# MCUStudent.net
KiCad netlist of a schematic drawn in Altium Designer
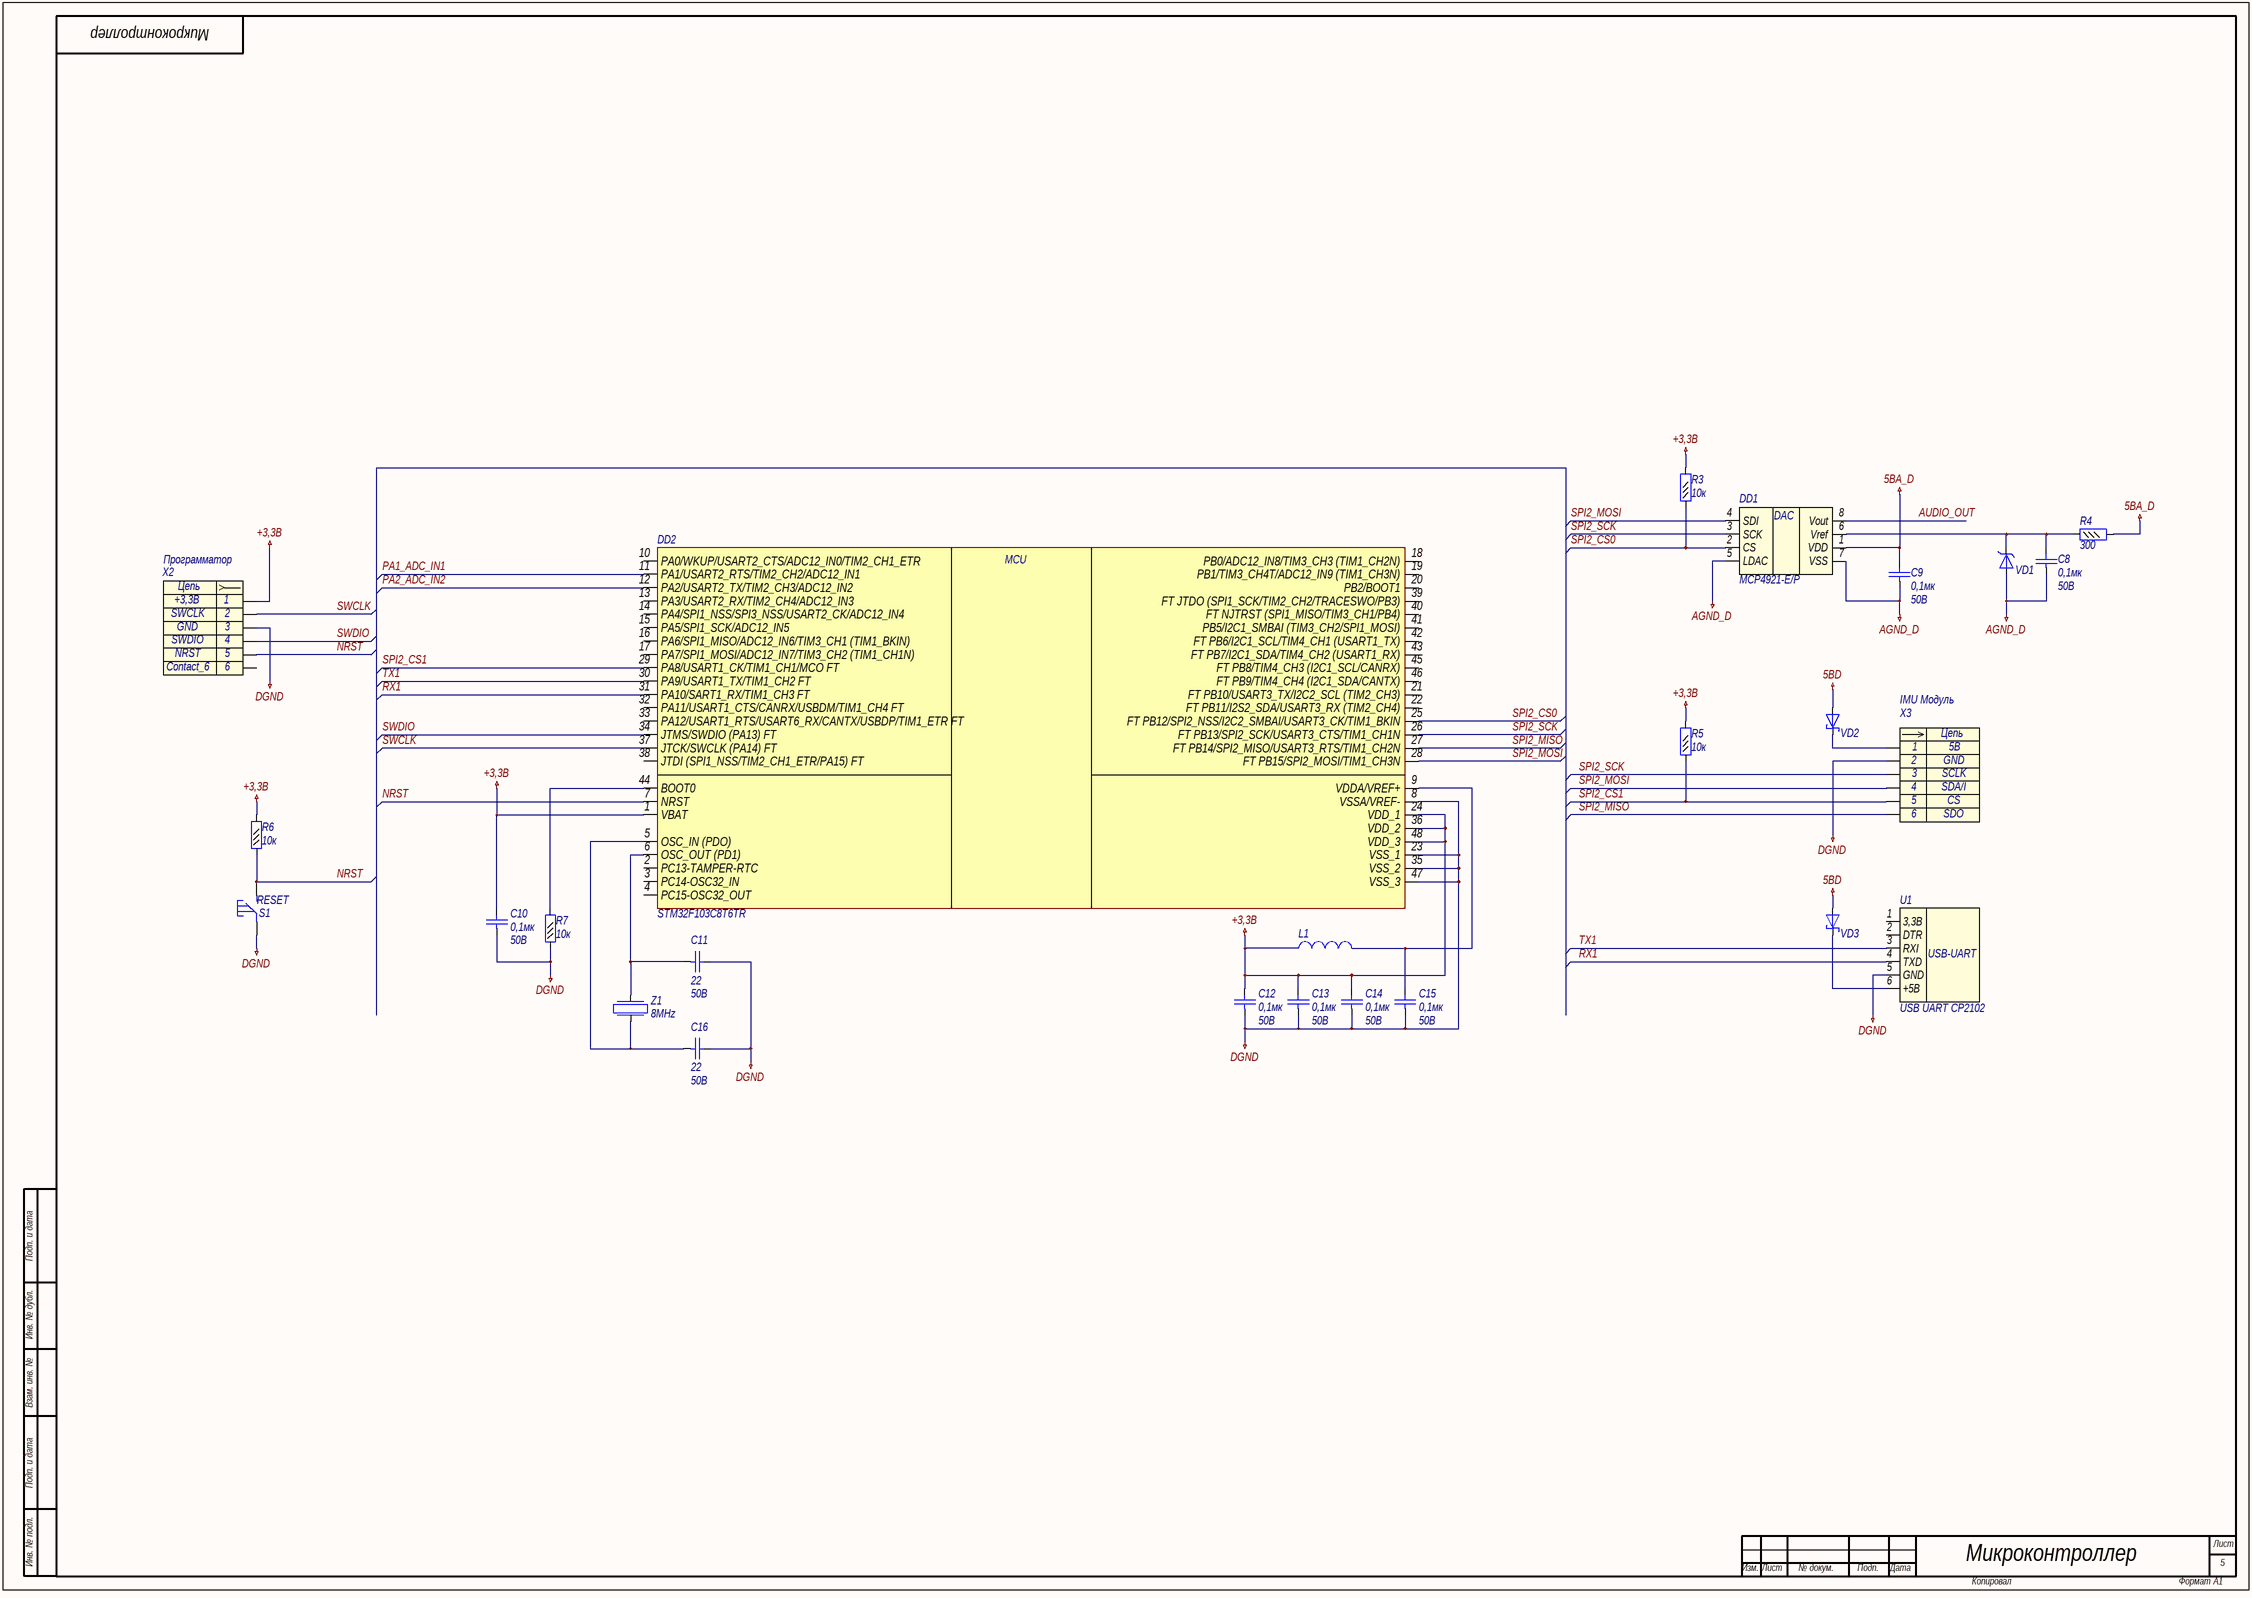
[diagram p0: MCUStudent.SchDoc]

(export (version "E")
  (design (tool "Eeschema 10.0.6"))
  (components
    (comp (ref "C8")
      (value "0,1мк")
      (footprint "C0603")
      (description "Конденсатор")
      (fields
        (field (name "VOLTAGE") "50B")
        (field (name "PART NUMBER") "GRM188R71H104KA93D")
        (field (name "Comment") "Capacitor")
      )
      (libsource (lib "MOP44") (part "Capacitor"))
    )
    (comp (ref "C9")
      (value "0,1мк")
      (footprint "C0603")
      (description "Конденсатор")
      (fields
        (field (name "VOLTAGE") "50B")
        (field (name "PART NUMBER") "GRM188R71H104KA93D")
        (field (name "Comment") "Capacitor")
      )
      (libsource (lib "MOP44") (part "Capacitor"))
    )
    (comp (ref "C10")
      (value "0,1мк")
      (footprint "C0603")
      (description "Конденсатор")
      (fields
        (field (name "VOLTAGE") "50B")
        (field (name "PART NUMBER") "GRM188R71H104KA93D")
        (field (name "Comment") "Capacitor")
      )
      (libsource (lib "MOP44") (part "Capacitor"))
    )
    (comp (ref "C11")
      (value "22")
      (footprint "C0603")
      (description "Конденсатор")
      (fields
        (field (name "VOLTAGE") "50B")
        (field (name "PART NUMBER") "CC0603JRNPO9BN220")
        (field (name "Comment") "Capacitor")
      )
      (libsource (lib "MOP44") (part "Capacitor"))
    )
    (comp (ref "C12")
      (value "0,1мк")
      (footprint "C0603")
      (description "Конденсатор")
      (fields
        (field (name "VOLTAGE") "50B")
        (field (name "PART NUMBER") "GRM188R71H104KA93D")
        (field (name "Comment") "Capacitor")
      )
      (libsource (lib "MOP44") (part "Capacitor"))
    )
    (comp (ref "C13")
      (value "0,1мк")
      (footprint "C0603")
      (description "Конденсатор")
      (fields
        (field (name "VOLTAGE") "50B")
        (field (name "PART NUMBER") "GRM188R71H104KA93D")
        (field (name "Comment") "Capacitor")
      )
      (libsource (lib "MOP44") (part "Capacitor"))
    )
    (comp (ref "C14")
      (value "0,1мк")
      (footprint "C0603")
      (description "Конденсатор")
      (fields
        (field (name "VOLTAGE") "50B")
        (field (name "PART NUMBER") "GRM188R71H104KA93D")
        (field (name "Comment") "Capacitor")
      )
      (libsource (lib "MOP44") (part "Capacitor"))
    )
    (comp (ref "C15")
      (value "0,1мк")
      (footprint "C0603")
      (description "Конденсатор")
      (fields
        (field (name "VOLTAGE") "50B")
        (field (name "PART NUMBER") "GRM188R71H104KA93D")
        (field (name "Comment") "Capacitor")
      )
      (libsource (lib "MOP44") (part "Capacitor"))
    )
    (comp (ref "C16")
      (value "22")
      (footprint "C0603")
      (description "Конденсатор")
      (fields
        (field (name "VOLTAGE") "50B")
        (field (name "PART NUMBER") "CC0603JRNPO9BN220")
        (field (name "Comment") "Capacitor")
      )
      (libsource (lib "MOP44") (part "Capacitor"))
    )
    (comp (ref "DD1")
      (value "MCP4921-E/P")
      (footprint "SO8")
      (description "12-Bit DAC with SPI™ Interface")
      (libsource (lib "MOP44") (part "MCP4921-E/P"))
    )
    (comp (ref "DD2")
      (value "STM32F103C8T6TR")
      (footprint "LQFP48")
      (fields (field (name "PART NUMBER") "STM32F103C8T6TR"))
      (libsource (lib "MOP44") (part "STM32F103C8T6TR"))
    )
    (comp (ref "L1")
      (value "Inductor")
      (footprint "L0603")
      (description "EMI Suppression Filter")
      (fields (field (name "PART NUMBER") "BLM18PG181SN1D"))
      (libsource (lib "MOP44") (part "Inductor"))
    )
    (comp (ref "R3")
      (value "10к")
      (footprint "R0603")
      (description "Резистор")
      (fields (field (name "PART NUMBER") "RC0603FR-0710KL") (field (name "POWER") "0,062Вт"))
      (libsource (lib "MOP44") (part "Resistor_0,062Вт"))
    )
    (comp (ref "R4")
      (value "300")
      (footprint "R0603")
      (description "Резистор")
      (fields (field (name "PART NUMBER") "RC0603FR-07300RL") (field (name "POWER") "0,062Вт"))
      (libsource (lib "") (part "Resistor_0,062Вт_1"))
    )
    (comp (ref "R5")
      (value "10к")
      (footprint "R0603")
      (description "Резистор")
      (fields (field (name "PART NUMBER") "RC0603FR-0710KL") (field (name "POWER") "0,062Вт"))
      (libsource (lib "MOP44") (part "Resistor_0,062Вт"))
    )
    (comp (ref "R6")
      (value "10к")
      (footprint "R0603")
      (description "Резистор")
      (fields (field (name "PART NUMBER") "RC0603FR-0710KL") (field (name "POWER") "0,062Вт"))
      (libsource (lib "MOP44") (part "Resistor_0,062Вт"))
    )
    (comp (ref "R7")
      (value "10к")
      (footprint "R0603")
      (description "Резистор")
      (fields (field (name "PART NUMBER") "RC0603FR-0710KL") (field (name "POWER") "0,062Вт"))
      (libsource (lib "MOP44") (part "Resistor_0,062Вт"))
    )
    (comp (ref "S1")
      (value "RESET")
      (footprint "Button_SMD")
      (description "Кнопка")
      (libsource (lib "MOP44") (part "Button"))
    )
    (comp (ref "U1")
      (value "USB UART")
      (footprint "USB UART CP2102")
      (description "USB UART module cp2102")
      (fields (field (name "PART NAME") "USB UART CP2102"))
      (libsource (lib "MOP44") (part "USB UART"))
    )
    (comp (ref "VD1")
      (value "LM4040BIM3-2.5/NOPB")
      (footprint "SOT23-3")
      (description "Прецезионный источник опорного напряжения")
      (libsource (lib "MOP44") (part "LM4040BIM3-2.5/NOPB"))
    )
    (comp (ref "VD2")
      (value "DiodeSchottky")
      (footprint "SOD-523")
      (description "Диод Шоттки")
      (fields (field (name "PART NUMBER") "PMEG2010AEB.115"))
      (libsource (lib "MOP44") (part "DiodeSchottky"))
    )
    (comp (ref "VD3")
      (value "DiodeSchottky")
      (footprint "SOD-523")
      (description "Диод Шоттки")
      (fields (field (name "PART NUMBER") "PMEG2010AEB.115"))
      (libsource (lib "MOP44") (part "DiodeSchottky"))
    )
    (comp (ref "X2")
      (value "Программатор")
      (footprint "PLS2-6")
      (description "Разъем - 6 конт. розетка")
      (libsource (lib "MOP44") (part "Header_6_sct"))
    )
    (comp (ref "X3")
      (value "IMU Модуль")
      (footprint "PLS-6")
      (description "Разъем - 6 конт. вилка")
      (fields (field (name "PART NUMBER") "MPU-9250"))
      (libsource (lib "MOP44") (part "Header_6_plg"))
    )
    (comp (ref "Z1")
      (value "Crystal")
      (footprint "HC-49S")
      (description "Кварцевый резонатор")
      (fields (field (name "FREQUENCE") "8MHz") (field (name "PART NUMBER") "8.000MHzHC-49US"))
      (libsource (lib "MOP44") (part "Crystal"))
    )
  )
  (nets
    (net (code "1") (name "+3,3В") (class "Default")
      (node (ref "C10") (pin "2") (pinfunction "2_2") (pintype "passive"))
      (node (ref "C12") (pin "2") (pinfunction "2_2") (pintype "passive"))
      (node (ref "C13") (pin "2") (pinfunction "2_2") (pintype "passive"))
      (node (ref "C14") (pin "2") (pinfunction "2_2") (pintype "passive"))
      (node (ref "DD2") (pin "1") (pinfunction "VBAT_1") (pintype "passive"))
      (node (ref "DD2") (pin "24") (pinfunction "VDD_1_24") (pintype "passive"))
      (node (ref "DD2") (pin "36") (pinfunction "VDD_2_36") (pintype "passive"))
      (node (ref "DD2") (pin "48") (pinfunction "VDD_3_48") (pintype "passive"))
      (node (ref "L1") (pin "1") (pinfunction "1_1") (pintype "passive"))
      (node (ref "R3") (pin "2") (pinfunction "2_2") (pintype "passive"))
      (node (ref "R5") (pin "2") (pinfunction "2_2") (pintype "passive"))
      (node (ref "R6") (pin "2") (pinfunction "2_2") (pintype "passive"))
      (node (ref "X2") (pin "1") (pinfunction "1_1") (pintype "passive"))
    )
    (net (code "2") (name "/AUDIO_OUT") (class "Default")
      (node (ref "DD1") (pin "8") (pinfunction "Vout_8") (pintype "power_in"))
    )
    (net (code "3") (name "/NRST") (class "Default")
      (node (ref "DD2") (pin "7") (pinfunction "NRST_7") (pintype "passive"))
      (node (ref "R6") (pin "1") (pinfunction "1_1") (pintype "passive"))
      (node (ref "S1") (pin "4") (pinfunction "4_4") (pintype "passive"))
      (node (ref "X2") (pin "5") (pinfunction "5_5") (pintype "passive"))
    )
    (net (code "4") (name "/PA1_ADC_IN1") (class "Default")
      (node (ref "DD2") (pin "11") (pinfunction "PA1/USART2_RTS/TIM2_CH2/ADC12_IN1_11") (pintype "passive"))
    )
    (net (code "5") (name "/PA2_ADC_IN2") (class "Default")
      (node (ref "DD2") (pin "12") (pinfunction "PA2/USART2_TX/TIM2_CH3/ADC12_IN2_12") (pintype "passive"))
    )
    (net (code "6") (name "/RX1") (class "Default")
      (node (ref "DD2") (pin "31") (pinfunction "PA10/SART1_RX/TIM1_CH3_FT_31") (pintype "passive"))
      (node (ref "U1") (pin "4") (pinfunction "TXD_4") (pintype "power_in"))
    )
    (net (code "7") (name "/SPI2_CS0") (class "Default")
      (node (ref "DD1") (pin "2") (pinfunction "CS_2") (pintype "power_in"))
      (node (ref "DD2") (pin "25") (pinfunction "FT_PB12/SPI2_NSS/I2C2_SMBAI/USART3_CK/TIM1_BKIN_25") (pintype "passive"))
      (node (ref "R3") (pin "1") (pinfunction "1_1") (pintype "passive"))
    )
    (net (code "8") (name "/SPI2_CS1") (class "Default")
      (node (ref "DD2") (pin "29") (pinfunction "PA8/USART1_CK/TIM1_CH1/MCO_FT_29") (pintype "passive"))
      (node (ref "R5") (pin "1") (pinfunction "1_1") (pintype "passive"))
      (node (ref "X3") (pin "5") (pinfunction "5_5") (pintype "passive"))
    )
    (net (code "9") (name "/SPI2_MISO") (class "Default")
      (node (ref "DD2") (pin "27") (pinfunction "FT_PB14/SPI2_MISO/USART3_RTS/TIM1_CH2N_27") (pintype "passive"))
      (node (ref "X3") (pin "6") (pinfunction "6_6") (pintype "passive"))
    )
    (net (code "10") (name "/SPI2_MOSI") (class "Default")
      (node (ref "DD1") (pin "4") (pinfunction "SDI_4") (pintype "power_in"))
      (node (ref "DD2") (pin "28") (pinfunction "FT_PB15/SPI2_MOSI/TIM1_CH3N_28") (pintype "passive"))
      (node (ref "X3") (pin "4") (pinfunction "4_4") (pintype "passive"))
    )
    (net (code "11") (name "/SPI2_SCK") (class "Default")
      (node (ref "DD1") (pin "3") (pinfunction "SCK_3") (pintype "power_in"))
      (node (ref "DD2") (pin "26") (pinfunction "FT_PB13/SPI2_SCK/USART3_CTS/TIM1_CH1N_26") (pintype "passive"))
      (node (ref "X3") (pin "3") (pinfunction "3_3") (pintype "passive"))
    )
    (net (code "12") (name "/SWCLK") (class "Default")
      (node (ref "DD2") (pin "37") (pinfunction "JTCK/SWCLK_(PA14)_FT_37") (pintype "passive"))
      (node (ref "X2") (pin "2") (pinfunction "2_2") (pintype "passive"))
    )
    (net (code "13") (name "/SWDIO") (class "Default")
      (node (ref "DD2") (pin "34") (pinfunction "JTMS/SWDIO_(PA13)_FT_34") (pintype "passive"))
      (node (ref "X2") (pin "4") (pinfunction "4_4") (pintype "passive"))
    )
    (net (code "14") (name "/TX1") (class "Default")
      (node (ref "DD2") (pin "30") (pinfunction "PA9/USART1_TX/TIM1_CH2_FT_30") (pintype "passive"))
      (node (ref "U1") (pin "3") (pinfunction "RXI_3") (pintype "power_in"))
    )
    (net (code "15") (name "5BA_D") (class "Default")
      (node (ref "C9") (pin "2") (pinfunction "2_2") (pintype "passive"))
      (node (ref "DD1") (pin "1") (pinfunction "VDD_1") (pintype "power_in"))
      (node (ref "R4") (pin "2") (pinfunction "2_2") (pintype "passive"))
    )
    (net (code "16") (name "5BD") (class "Default")
      (node (ref "VD2") (pin "2") (pinfunction "A_2") (pintype "passive"))
      (node (ref "VD3") (pin "2") (pinfunction "A_2") (pintype "passive"))
    )
    (net (code "17") (name "AGND_D") (class "Default")
      (node (ref "C8") (pin "1") (pinfunction "1_1") (pintype "passive"))
      (node (ref "C9") (pin "1") (pinfunction "1_1") (pintype "passive"))
      (node (ref "DD1") (pin "5") (pinfunction "LDAC_5") (pintype "power_in"))
      (node (ref "DD1") (pin "7") (pinfunction "VSS_7") (pintype "power_in"))
      (node (ref "VD1") (pin "2") (pinfunction "A_2") (pintype "passive"))
    )
    (net (code "18") (name "DGND") (class "Default")
      (node (ref "C10") (pin "1") (pinfunction "1_1") (pintype "passive"))
      (node (ref "C11") (pin "2") (pinfunction "2_2") (pintype "passive"))
      (node (ref "C12") (pin "1") (pinfunction "1_1") (pintype "passive"))
      (node (ref "C13") (pin "1") (pinfunction "1_1") (pintype "passive"))
      (node (ref "C14") (pin "1") (pinfunction "1_1") (pintype "passive"))
      (node (ref "C15") (pin "1") (pinfunction "1_1") (pintype "passive"))
      (node (ref "C16") (pin "2") (pinfunction "2_2") (pintype "passive"))
      (node (ref "DD2") (pin "23") (pinfunction "VSS_1_23") (pintype "passive"))
      (node (ref "DD2") (pin "35") (pinfunction "VSS_2_35") (pintype "passive"))
      (node (ref "DD2") (pin "47") (pinfunction "VSS_3_47") (pintype "passive"))
      (node (ref "DD2") (pin "8") (pinfunction "VSSA/VREF-_8") (pintype "passive"))
      (node (ref "R7") (pin "1") (pinfunction "1_1") (pintype "passive"))
      (node (ref "S1") (pin "1") (pinfunction "1_1") (pintype "passive"))
      (node (ref "U1") (pin "5") (pinfunction "GND_5") (pintype "power_in"))
      (node (ref "X2") (pin "3") (pinfunction "3_3") (pintype "passive"))
      (node (ref "X3") (pin "2") (pinfunction "2_2") (pintype "passive"))
    )
    (net (code "19") (name "Net-(DD1-Vref)") (class "Default")
      (node (ref "C8") (pin "2") (pinfunction "2_2") (pintype "passive"))
      (node (ref "DD1") (pin "6") (pinfunction "Vref_6") (pintype "power_in"))
      (node (ref "R4") (pin "1") (pinfunction "1_1") (pintype "passive"))
      (node (ref "VD1") (pin "1") (pinfunction "K_1") (pintype "passive"))
    )
    (net (code "20") (name "Net-(DD2-BOOT0)") (class "Default")
      (node (ref "DD2") (pin "44") (pinfunction "BOOT0_44") (pintype "passive"))
      (node (ref "R7") (pin "2") (pinfunction "2_2") (pintype "passive"))
    )
    (net (code "21") (name "Net-(DD2-OSC_IN_(PDO))") (class "Default")
      (node (ref "C16") (pin "1") (pinfunction "1_1") (pintype "passive"))
      (node (ref "DD2") (pin "5") (pinfunction "OSC_IN_(PDO)_5") (pintype "passive"))
      (node (ref "Z1") (pin "1") (pinfunction "1_1") (pintype "passive"))
    )
    (net (code "22") (name "Net-(DD2-OSC_OUT_(PD1))") (class "Default")
      (node (ref "C11") (pin "1") (pinfunction "1_1") (pintype "passive"))
      (node (ref "DD2") (pin "6") (pinfunction "OSC_OUT_(PD1)_6") (pintype "passive"))
      (node (ref "Z1") (pin "2") (pinfunction "2_2") (pintype "passive"))
    )
    (net (code "23") (name "Net-(DD2-VDDA{slash}VREF+)") (class "Default")
      (node (ref "C15") (pin "2") (pinfunction "2_2") (pintype "passive"))
      (node (ref "DD2") (pin "9") (pinfunction "VDDA/VREF+_9") (pintype "passive"))
      (node (ref "L1") (pin "2") (pinfunction "2_2") (pintype "passive"))
    )
    (net (code "24") (name "Net-(U1-+5B)") (class "Default")
      (node (ref "U1") (pin "6") (pinfunction "+5B_6") (pintype "power_in"))
      (node (ref "VD3") (pin "1") (pinfunction "K_1") (pintype "passive"))
    )
    (net (code "25") (name "Net-(VD2-K)") (class "Default")
      (node (ref "VD2") (pin "1") (pinfunction "K_1") (pintype "passive"))
      (node (ref "X3") (pin "1") (pinfunction "1_1") (pintype "passive"))
    )
    (net (code "26") (name "unconnected-(DD2-FT_JTDO_(SPI1_SCK{slash}TIM2_CH2{slash}TRACESWO{slash}PB3)-Pad39)") (class "Default")
      (node (ref "DD2") (pin "39") (pinfunction "FT_JTDO_(SPI1_SCK/TIM2_CH2/TRACESWO/PB3)_39") (pintype "passive"))
    )
    (net (code "27") (name "unconnected-(DD2-FT_NJTRST_(SPI1_MISO{slash}TIM3_CH1{slash}PB4)-Pad40)") (class "Default")
      (node (ref "DD2") (pin "40") (pinfunction "FT_NJTRST_(SPI1_MISO/TIM3_CH1/PB4)_40") (pintype "passive"))
    )
    (net (code "28") (name "unconnected-(DD2-FT_PB6{slash}I2C1_SCL{slash}TIM4_CH1_(USART1_TX)-Pad42)") (class "Default")
      (node (ref "DD2") (pin "42") (pinfunction "FT_PB6/I2C1_SCL/TIM4_CH1_(USART1_TX)_42") (pintype "passive"))
    )
    (net (code "29") (name "unconnected-(DD2-FT_PB7{slash}I2C1_SDA{slash}TIM4_CH2_(USART1_RX)-Pad43)") (class "Default")
      (node (ref "DD2") (pin "43") (pinfunction "FT_PB7/I2C1_SDA/TIM4_CH2_(USART1_RX)_43") (pintype "passive"))
    )
    (net (code "30") (name "unconnected-(DD2-FT_PB8{slash}TIM4_CH3_(I2C1_SCL{slash}CANRX)-Pad45)") (class "Default")
      (node (ref "DD2") (pin "45") (pinfunction "FT_PB8/TIM4_CH3_(I2C1_SCL/CANRX)_45") (pintype "passive"))
    )
    (net (code "31") (name "unconnected-(DD2-FT_PB9{slash}TIM4_CH4_(I2C1_SDA{slash}CANTX)-Pad46)") (class "Default")
      (node (ref "DD2") (pin "46") (pinfunction "FT_PB9/TIM4_CH4_(I2C1_SDA/CANTX)_46") (pintype "passive"))
    )
    (net (code "32") (name "unconnected-(DD2-FT_PB10{slash}USART3_TX{slash}I2C2_SCL_(TIM2_CH3)-Pad21)") (class "Default")
      (node (ref "DD2") (pin "21") (pinfunction "FT_PB10/USART3_TX/I2C2_SCL_(TIM2_CH3)_21") (pintype "passive"))
    )
    (net (code "33") (name "unconnected-(DD2-FT_PB11{slash}I2S2_SDA{slash}USART3_RX_(TIM2_CH4)-Pad22)") (class "Default")
      (node (ref "DD2") (pin "22") (pinfunction "FT_PB11/I2S2_SDA/USART3_RX_(TIM2_CH4)_22") (pintype "passive"))
    )
    (net (code "34") (name "unconnected-(DD2-JTDI_(SPI1_NSS{slash}TIM2_CH1_ETR{slash}PA15)_FT-Pad38)") (class "Default")
      (node (ref "DD2") (pin "38") (pinfunction "JTDI_(SPI1_NSS/TIM2_CH1_ETR/PA15)_FT_38") (pintype "passive"))
    )
    (net (code "35") (name "unconnected-(DD2-PA0{slash}WKUP{slash}USART2_CTS{slash}ADC12_IN0{slash}TIM2_CH1_ETR-Pad10)") (class "Default")
      (node (ref "DD2") (pin "10") (pinfunction "PA0/WKUP/USART2_CTS/ADC12_IN0/TIM2_CH1_ETR_10") (pintype "passive"))
    )
    (net (code "36") (name "unconnected-(DD2-PA3{slash}USART2_RX{slash}TIM2_CH4{slash}ADC12_IN3-Pad13)") (class "Default")
      (node (ref "DD2") (pin "13") (pinfunction "PA3/USART2_RX/TIM2_CH4/ADC12_IN3_13") (pintype "passive"))
    )
    (net (code "37") (name "unconnected-(DD2-PA4{slash}SPI1_NSS{slash}SPI3_NSS{slash}USART2_CK{slash}ADC12_IN4-Pad14)") (class "Default")
      (node (ref "DD2") (pin "14") (pinfunction "PA4/SPI1_NSS/SPI3_NSS/USART2_CK/ADC12_IN4_14") (pintype "passive"))
    )
    (net (code "38") (name "unconnected-(DD2-PA5{slash}SPI1_SCK{slash}ADC12_IN5-Pad15)") (class "Default")
      (node (ref "DD2") (pin "15") (pinfunction "PA5/SPI1_SCK/ADC12_IN5_15") (pintype "passive"))
    )
    (net (code "39") (name "unconnected-(DD2-PA6{slash}SPI1_MISO{slash}ADC12_IN6{slash}TIM3_CH1_(TIM1_BKIN)-Pad16)") (class "Default")
      (node (ref "DD2") (pin "16") (pinfunction "PA6/SPI1_MISO/ADC12_IN6/TIM3_CH1_(TIM1_BKIN)_16") (pintype "passive"))
    )
    (net (code "40") (name "unconnected-(DD2-PA7{slash}SPI1_MOSI{slash}ADC12_IN7{slash}TIM3_CH2_(TIM1_CH1N)-Pad17)") (class "Default")
      (node (ref "DD2") (pin "17") (pinfunction "PA7/SPI1_MOSI/ADC12_IN7/TIM3_CH2_(TIM1_CH1N)_17") (pintype "passive"))
    )
    (net (code "41") (name "unconnected-(DD2-PA11{slash}USART1_CTS{slash}CANRX{slash}USBDM{slash}TIM1_CH4_FT-Pad32)") (class "Default")
      (node (ref "DD2") (pin "32") (pinfunction "PA11/USART1_CTS/CANRX/USBDM/TIM1_CH4_FT_32") (pintype "passive"))
    )
    (net (code "42") (name "unconnected-(DD2-PA12{slash}USART1_RTS{slash}USART6_RX{slash}CANTX{slash}USBDP{slash}TIM1_ETR_FT-Pad33)") (class "Default")
      (node (ref "DD2") (pin "33") (pinfunction "PA12/USART1_RTS/USART6_RX/CANTX/USBDP/TIM1_ETR_FT_33") (pintype "passive"))
    )
    (net (code "43") (name "unconnected-(DD2-PB0{slash}ADC12_IN8{slash}TIM3_CH3_(TIM1_CH2N)-Pad18)") (class "Default")
      (node (ref "DD2") (pin "18") (pinfunction "PB0/ADC12_IN8/TIM3_CH3_(TIM1_CH2N)_18") (pintype "passive"))
    )
    (net (code "44") (name "unconnected-(DD2-PB1{slash}TIM3_CH4T{slash}ADC12_IN9_(TIM1_CH3N)-Pad19)") (class "Default")
      (node (ref "DD2") (pin "19") (pinfunction "PB1/TIM3_CH4T/ADC12_IN9_(TIM1_CH3N)_19") (pintype "passive"))
    )
    (net (code "45") (name "unconnected-(DD2-PB2{slash}BOOT1-Pad20)") (class "Default")
      (node (ref "DD2") (pin "20") (pinfunction "PB2/BOOT1_20") (pintype "passive"))
    )
    (net (code "46") (name "unconnected-(DD2-PB5{slash}I2C1_SMBAI_(TIM3_CH2{slash}SPI1_MOSI)-Pad41)") (class "Default")
      (node (ref "DD2") (pin "41") (pinfunction "PB5/I2C1_SMBAI_(TIM3_CH2/SPI1_MOSI)_41") (pintype "passive"))
    )
    (net (code "47") (name "unconnected-(DD2-PC13-TAMPER-RTC-Pad2)") (class "Default")
      (node (ref "DD2") (pin "2") (pinfunction "PC13-TAMPER-RTC_2") (pintype "passive"))
    )
    (net (code "48") (name "unconnected-(DD2-PC14-OSC32_IN-Pad3)") (class "Default")
      (node (ref "DD2") (pin "3") (pinfunction "PC14-OSC32_IN_3") (pintype "passive"))
    )
    (net (code "49") (name "unconnected-(DD2-PC15-OSC32_OUT-Pad4)") (class "Default")
      (node (ref "DD2") (pin "4") (pinfunction "PC15-OSC32_OUT_4") (pintype "passive"))
    )
    (net (code "50") (name "unconnected-(U1-3,3B-Pad1)") (class "Default")
      (node (ref "U1") (pin "1") (pinfunction "3,3B_1") (pintype "power_in"))
    )
    (net (code "51") (name "unconnected-(U1-DTR-Pad2)") (class "Default")
      (node (ref "U1") (pin "2") (pinfunction "DTR_2") (pintype "power_in"))
    )
    (net (code "52") (name "unconnected-(X2-Pad6)") (class "Default")
      (node (ref "X2") (pin "6") (pinfunction "6_6") (pintype "passive"))
    )
  )
)
